# Ports_2.net
KiCad netlist of a schematic drawn in Altium Designer
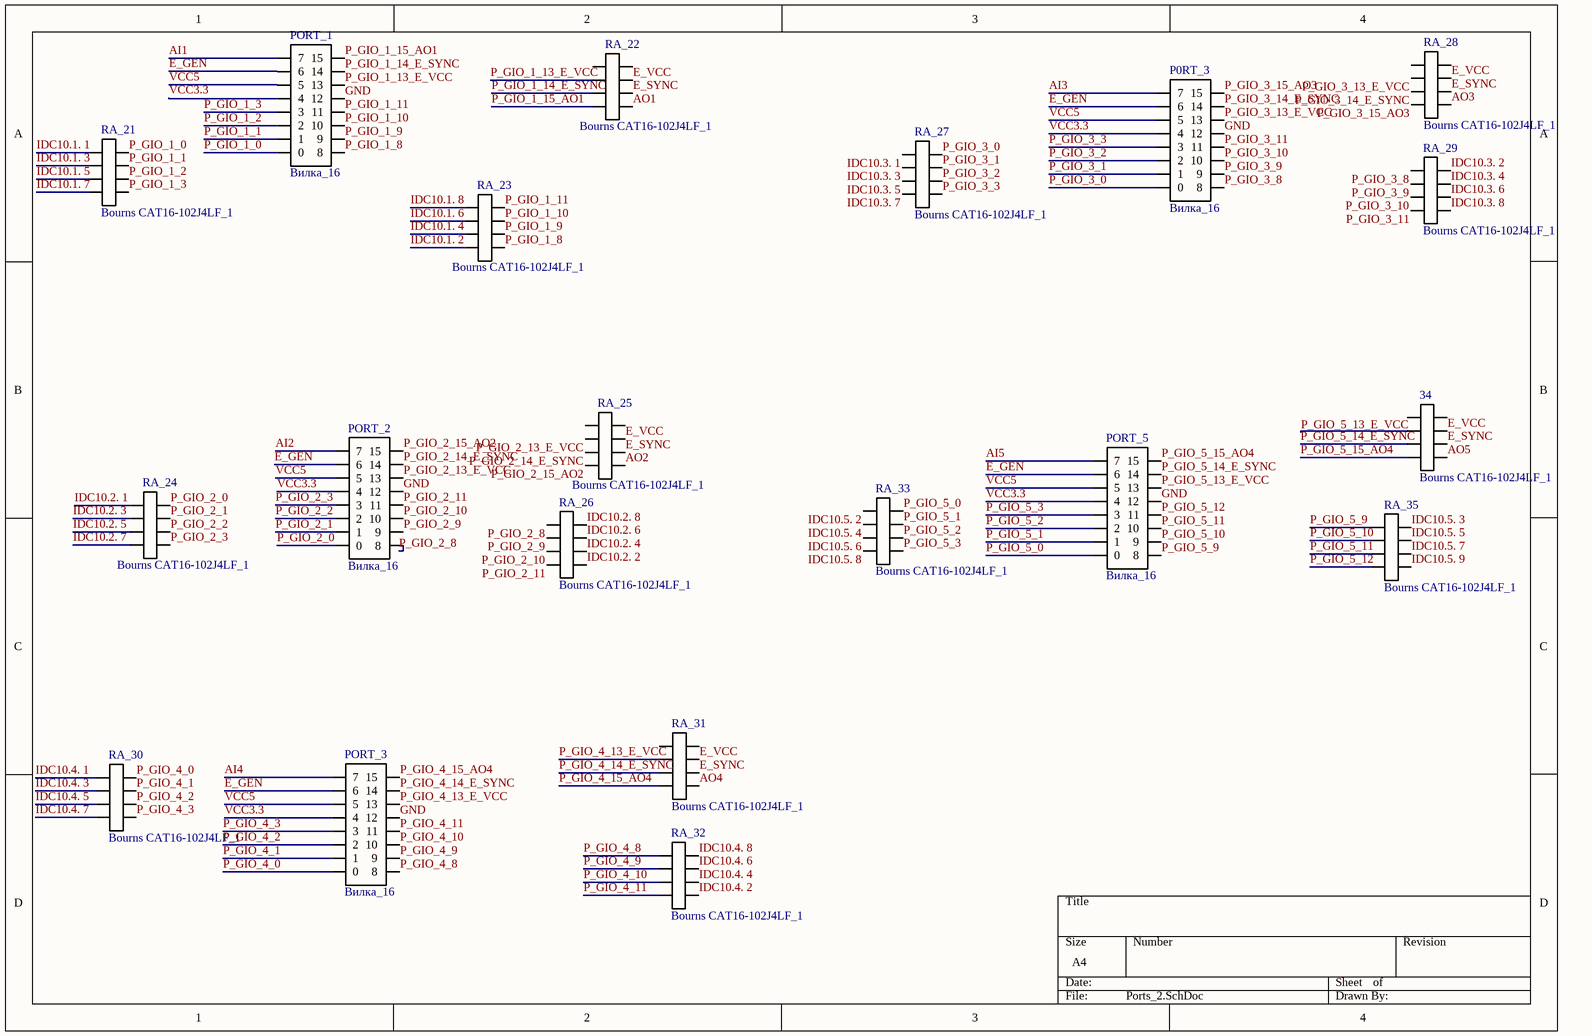
[diagram p0: Ports_2.SchDoc]

(export (version "E")
  (design (tool "Eeschema 10.0.6"))
  (components
    (comp (ref "34")
      (value "Bourns CAT16-102J4LF_1")
      (footprint "PcbLib1:CAT16-102J4LF_2")
      (libsource (lib "Library") (part "Bourns CAT16-102J4LF_1"))
    )
    (comp (ref "P0RT_3")
      (value "Вилка_16")
      (footprint "DS1013-16")
      (description "16_pin")
      (libsource (lib "Library") (part "DS1013-16"))
    )
    (comp (ref "PORT_1")
      (value "Вилка_16")
      (footprint "DS1013-16")
      (description "16_pin")
      (libsource (lib "Library") (part "DS1013-16"))
    )
    (comp (ref "PORT_2")
      (value "Вилка_16")
      (footprint "DS1013-16")
      (description "16_pin")
      (libsource (lib "Library") (part "DS1013-16"))
    )
    (comp (ref "PORT_3")
      (value "Вилка_16")
      (footprint "DS1013-16")
      (description "16_pin")
      (libsource (lib "Library") (part "DS1013-16"))
    )
    (comp (ref "PORT_5")
      (value "Вилка_16")
      (footprint "DS1013-16")
      (description "16_pin")
      (libsource (lib "Library") (part "DS1013-16"))
    )
    (comp (ref "RA_21")
      (value "Bourns CAT16-102J4LF_1")
      (footprint "PcbLib1:CAT16-102J4LF_2")
      (libsource (lib "Library") (part "Bourns CAT16-102J4LF_1"))
    )
    (comp (ref "RA_22")
      (value "Bourns CAT16-102J4LF_1")
      (footprint "PcbLib1:CAT16-102J4LF_2")
      (libsource (lib "Library") (part "Bourns CAT16-102J4LF_1"))
    )
    (comp (ref "RA_23")
      (value "Bourns CAT16-102J4LF_1")
      (footprint "PcbLib1:CAT16-102J4LF_2")
      (libsource (lib "Library") (part "Bourns CAT16-102J4LF_1"))
    )
    (comp (ref "RA_24")
      (value "Bourns CAT16-102J4LF_1")
      (footprint "PcbLib1:CAT16-102J4LF_2")
      (libsource (lib "Library") (part "Bourns CAT16-102J4LF_1"))
    )
    (comp (ref "RA_25")
      (value "Bourns CAT16-102J4LF_1")
      (footprint "PcbLib1:CAT16-102J4LF_2")
      (libsource (lib "Library") (part "Bourns CAT16-102J4LF_1"))
    )
    (comp (ref "RA_26")
      (value "Bourns CAT16-102J4LF_1")
      (footprint "PcbLib1:CAT16-102J4LF_2")
      (libsource (lib "Library") (part "Bourns CAT16-102J4LF_1"))
    )
    (comp (ref "RA_27")
      (value "Bourns CAT16-102J4LF_1")
      (footprint "PcbLib1:CAT16-102J4LF_2")
      (libsource (lib "Library") (part "Bourns CAT16-102J4LF_1"))
    )
    (comp (ref "RA_28")
      (value "Bourns CAT16-102J4LF_1")
      (footprint "PcbLib1:CAT16-102J4LF_2")
      (libsource (lib "Library") (part "Bourns CAT16-102J4LF_1"))
    )
    (comp (ref "RA_29")
      (value "Bourns CAT16-102J4LF_1")
      (footprint "PcbLib1:CAT16-102J4LF_2")
      (libsource (lib "Library") (part "Bourns CAT16-102J4LF_1"))
    )
    (comp (ref "RA_30")
      (value "Bourns CAT16-102J4LF_1")
      (footprint "PcbLib1:CAT16-102J4LF_2")
      (libsource (lib "Library") (part "Bourns CAT16-102J4LF_1"))
    )
    (comp (ref "RA_31")
      (value "Bourns CAT16-102J4LF_1")
      (footprint "PcbLib1:CAT16-102J4LF_2")
      (libsource (lib "Library") (part "Bourns CAT16-102J4LF_1"))
    )
    (comp (ref "RA_32")
      (value "Bourns CAT16-102J4LF_1")
      (footprint "PcbLib1:CAT16-102J4LF_2")
      (libsource (lib "Library") (part "Bourns CAT16-102J4LF_1"))
    )
    (comp (ref "RA_33")
      (value "Bourns CAT16-102J4LF_1")
      (footprint "PcbLib1:CAT16-102J4LF_2")
      (libsource (lib "Library") (part "Bourns CAT16-102J4LF_1"))
    )
    (comp (ref "RA_35")
      (value "Bourns CAT16-102J4LF_1")
      (footprint "PcbLib1:CAT16-102J4LF_2")
      (libsource (lib "Library") (part "Bourns CAT16-102J4LF_1"))
    )
  )
  (nets
    (net (code "1") (name "/AI1") (class "Default")
      (node (ref "PORT_1") (pin "7") (pinfunction "7_7") (pintype "passive"))
    )
    (net (code "2") (name "/AI2") (class "Default")
      (node (ref "PORT_2") (pin "7") (pinfunction "7_7") (pintype "passive"))
    )
    (net (code "3") (name "/AI3") (class "Default")
      (node (ref "P0RT_3") (pin "7") (pinfunction "7_7") (pintype "passive"))
    )
    (net (code "4") (name "/AI4") (class "Default")
      (node (ref "PORT_3") (pin "7") (pinfunction "7_7") (pintype "passive"))
    )
    (net (code "5") (name "/AI5") (class "Default")
      (node (ref "PORT_5") (pin "7") (pinfunction "7_7") (pintype "passive"))
    )
    (net (code "6") (name "/AO1") (class "Default")
      (node (ref "RA_22") (pin "4") (pinfunction "4_4") (pintype "passive"))
    )
    (net (code "7") (name "/AO2") (class "Default")
      (node (ref "RA_25") (pin "4") (pinfunction "4_4") (pintype "passive"))
    )
    (net (code "8") (name "/AO3") (class "Default")
      (node (ref "RA_28") (pin "0") (pinfunction "0_0") (pintype "passive"))
    )
    (net (code "9") (name "/AO4") (class "Default")
      (node (ref "RA_31") (pin "4") (pinfunction "4_4") (pintype "passive"))
    )
    (net (code "10") (name "/AO5") (class "Default")
      (node (ref "34") (pin "0") (pinfunction "0_0") (pintype "passive"))
    )
    (net (code "11") (name "/E_GEN") (class "Default")
      (node (ref "P0RT_3") (pin "6") (pinfunction "6_6") (pintype "passive"))
      (node (ref "PORT_1") (pin "6") (pinfunction "6_6") (pintype "passive"))
      (node (ref "PORT_2") (pin "6") (pinfunction "6_6") (pintype "passive"))
      (node (ref "PORT_3") (pin "6") (pinfunction "6_6") (pintype "passive"))
      (node (ref "PORT_5") (pin "6") (pinfunction "6_6") (pintype "passive"))
    )
    (net (code "12") (name "/E_SYNC") (class "Default")
      (node (ref "34") (pin "1") (pinfunction "1_1") (pintype "passive"))
      (node (ref "RA_22") (pin "5") (pinfunction "5_5") (pintype "passive"))
      (node (ref "RA_25") (pin "5") (pinfunction "5_5") (pintype "passive"))
      (node (ref "RA_28") (pin "1") (pinfunction "1_1") (pintype "passive"))
      (node (ref "RA_31") (pin "5") (pinfunction "5_5") (pintype "passive"))
    )
    (net (code "13") (name "/E_VCC") (class "Default")
      (node (ref "34") (pin "2") (pinfunction "2_2") (pintype "passive"))
      (node (ref "RA_22") (pin "6") (pinfunction "6_6") (pintype "passive"))
      (node (ref "RA_25") (pin "6") (pinfunction "6_6") (pintype "passive"))
      (node (ref "RA_28") (pin "2") (pinfunction "2_2") (pintype "passive"))
      (node (ref "RA_31") (pin "6") (pinfunction "6_6") (pintype "passive"))
    )
    (net (code "14") (name "/GND") (class "Default")
      (node (ref "P0RT_3") (pin "12") (pinfunction "12_12") (pintype "passive"))
      (node (ref "PORT_1") (pin "12") (pinfunction "12_12") (pintype "passive"))
      (node (ref "PORT_2") (pin "12") (pinfunction "12_12") (pintype "passive"))
      (node (ref "PORT_3") (pin "12") (pinfunction "12_12") (pintype "passive"))
      (node (ref "PORT_5") (pin "12") (pinfunction "12_12") (pintype "passive"))
    )
    (net (code "15") (name "/IDC10.1. 1") (class "Default")
      (node (ref "RA_21") (pin "4") (pinfunction "4_4") (pintype "passive"))
    )
    (net (code "16") (name "/IDC10.1. 2") (class "Default")
      (node (ref "RA_23") (pin "3") (pinfunction "3_3") (pintype "passive"))
    )
    (net (code "17") (name "/IDC10.1. 3") (class "Default")
      (node (ref "RA_21") (pin "5") (pinfunction "5_5") (pintype "passive"))
    )
    (net (code "18") (name "/IDC10.1. 4") (class "Default")
      (node (ref "RA_23") (pin "2") (pinfunction "2_2") (pintype "passive"))
    )
    (net (code "19") (name "/IDC10.1. 5") (class "Default")
      (node (ref "RA_21") (pin "6") (pinfunction "6_6") (pintype "passive"))
    )
    (net (code "20") (name "/IDC10.1. 6") (class "Default")
      (node (ref "RA_23") (pin "1") (pinfunction "1_1") (pintype "passive"))
    )
    (net (code "21") (name "/IDC10.1. 7") (class "Default")
      (node (ref "RA_21") (pin "7") (pinfunction "7_7") (pintype "passive"))
    )
    (net (code "22") (name "/IDC10.1. 8") (class "Default")
      (node (ref "RA_23") (pin "0") (pinfunction "0_0") (pintype "passive"))
    )
    (net (code "23") (name "/IDC10.2. 1") (class "Default")
      (node (ref "RA_24") (pin "0") (pinfunction "0_0") (pintype "passive"))
    )
    (net (code "24") (name "/IDC10.2. 2") (class "Default")
      (node (ref "RA_26") (pin "0") (pinfunction "0_0") (pintype "passive"))
    )
    (net (code "25") (name "/IDC10.2. 3") (class "Default")
      (node (ref "RA_24") (pin "1") (pinfunction "1_1") (pintype "passive"))
    )
    (net (code "26") (name "/IDC10.2. 4") (class "Default")
      (node (ref "RA_26") (pin "1") (pinfunction "1_1") (pintype "passive"))
    )
    (net (code "27") (name "/IDC10.2. 5") (class "Default")
      (node (ref "RA_24") (pin "2") (pinfunction "2_2") (pintype "passive"))
    )
    (net (code "28") (name "/IDC10.2. 6") (class "Default")
      (node (ref "RA_26") (pin "2") (pinfunction "2_2") (pintype "passive"))
    )
    (net (code "29") (name "/IDC10.2. 7") (class "Default")
      (node (ref "RA_24") (pin "3") (pinfunction "3_3") (pintype "passive"))
    )
    (net (code "30") (name "/IDC10.2. 8") (class "Default")
      (node (ref "RA_26") (pin "3") (pinfunction "3_3") (pintype "passive"))
    )
    (net (code "31") (name "/IDC10.3. 1") (class "Default")
      (node (ref "RA_27") (pin "4") (pinfunction "4_4") (pintype "passive"))
    )
    (net (code "32") (name "/IDC10.3. 2") (class "Default")
      (node (ref "RA_29") (pin "3") (pinfunction "3_3") (pintype "passive"))
    )
    (net (code "33") (name "/IDC10.3. 3") (class "Default")
      (node (ref "RA_27") (pin "5") (pinfunction "5_5") (pintype "passive"))
    )
    (net (code "34") (name "/IDC10.3. 4") (class "Default")
      (node (ref "RA_29") (pin "2") (pinfunction "2_2") (pintype "passive"))
    )
    (net (code "35") (name "/IDC10.3. 5") (class "Default")
      (node (ref "RA_27") (pin "6") (pinfunction "6_6") (pintype "passive"))
    )
    (net (code "36") (name "/IDC10.3. 6") (class "Default")
      (node (ref "RA_29") (pin "1") (pinfunction "1_1") (pintype "passive"))
    )
    (net (code "37") (name "/IDC10.3. 7") (class "Default")
      (node (ref "RA_27") (pin "7") (pinfunction "7_7") (pintype "passive"))
    )
    (net (code "38") (name "/IDC10.3. 8") (class "Default")
      (node (ref "RA_29") (pin "0") (pinfunction "0_0") (pintype "passive"))
    )
    (net (code "39") (name "/IDC10.4. 1") (class "Default")
      (node (ref "RA_30") (pin "4") (pinfunction "4_4") (pintype "passive"))
    )
    (net (code "40") (name "/IDC10.4. 2") (class "Default")
      (node (ref "RA_32") (pin "0") (pinfunction "0_0") (pintype "passive"))
    )
    (net (code "41") (name "/IDC10.4. 3") (class "Default")
      (node (ref "RA_30") (pin "5") (pinfunction "5_5") (pintype "passive"))
    )
    (net (code "42") (name "/IDC10.4. 4") (class "Default")
      (node (ref "RA_32") (pin "1") (pinfunction "1_1") (pintype "passive"))
    )
    (net (code "43") (name "/IDC10.4. 5") (class "Default")
      (node (ref "RA_30") (pin "6") (pinfunction "6_6") (pintype "passive"))
    )
    (net (code "44") (name "/IDC10.4. 6") (class "Default")
      (node (ref "RA_32") (pin "2") (pinfunction "2_2") (pintype "passive"))
    )
    (net (code "45") (name "/IDC10.4. 7") (class "Default")
      (node (ref "RA_30") (pin "7") (pinfunction "7_7") (pintype "passive"))
    )
    (net (code "46") (name "/IDC10.4. 8") (class "Default")
      (node (ref "RA_32") (pin "3") (pinfunction "3_3") (pintype "passive"))
    )
    (net (code "47") (name "/IDC10.5. 2") (class "Default")
      (node (ref "RA_33") (pin "4") (pinfunction "4_4") (pintype "passive"))
    )
    (net (code "48") (name "/IDC10.5. 3") (class "Default")
      (node (ref "RA_35") (pin "3") (pinfunction "3_3") (pintype "passive"))
    )
    (net (code "49") (name "/IDC10.5. 4") (class "Default")
      (node (ref "RA_33") (pin "5") (pinfunction "5_5") (pintype "passive"))
    )
    (net (code "50") (name "/IDC10.5. 5") (class "Default")
      (node (ref "RA_35") (pin "2") (pinfunction "2_2") (pintype "passive"))
    )
    (net (code "51") (name "/IDC10.5. 6") (class "Default")
      (node (ref "RA_33") (pin "6") (pinfunction "6_6") (pintype "passive"))
    )
    (net (code "52") (name "/IDC10.5. 7") (class "Default")
      (node (ref "RA_35") (pin "1") (pinfunction "1_1") (pintype "passive"))
    )
    (net (code "53") (name "/IDC10.5. 8") (class "Default")
      (node (ref "RA_33") (pin "7") (pinfunction "7_7") (pintype "passive"))
    )
    (net (code "54") (name "/IDC10.5. 9") (class "Default")
      (node (ref "RA_35") (pin "0") (pinfunction "0_0") (pintype "passive"))
    )
    (net (code "55") (name "/P_GIO_1_0") (class "Default")
      (node (ref "PORT_1") (pin "0") (pinfunction "0_0") (pintype "passive"))
      (node (ref "RA_21") (pin "3") (pinfunction "3_3") (pintype "passive"))
    )
    (net (code "56") (name "/P_GIO_1_1") (class "Default")
      (node (ref "PORT_1") (pin "1") (pinfunction "1_1") (pintype "passive"))
      (node (ref "RA_21") (pin "2") (pinfunction "2_2") (pintype "passive"))
    )
    (net (code "57") (name "/P_GIO_1_2") (class "Default")
      (node (ref "PORT_1") (pin "2") (pinfunction "2_2") (pintype "passive"))
      (node (ref "RA_21") (pin "1") (pinfunction "1_1") (pintype "passive"))
    )
    (net (code "58") (name "/P_GIO_1_3") (class "Default")
      (node (ref "PORT_1") (pin "3") (pinfunction "3_3") (pintype "passive"))
      (node (ref "RA_21") (pin "0") (pinfunction "0_0") (pintype "passive"))
    )
    (net (code "59") (name "/P_GIO_1_8") (class "Default")
      (node (ref "PORT_1") (pin "8") (pinfunction "8_8") (pintype "passive"))
      (node (ref "RA_23") (pin "4") (pinfunction "4_4") (pintype "passive"))
    )
    (net (code "60") (name "/P_GIO_1_9") (class "Default")
      (node (ref "PORT_1") (pin "9") (pinfunction "9_9") (pintype "passive"))
      (node (ref "RA_23") (pin "5") (pinfunction "5_5") (pintype "passive"))
    )
    (net (code "61") (name "/P_GIO_1_10") (class "Default")
      (node (ref "PORT_1") (pin "10") (pinfunction "10_10") (pintype "passive"))
      (node (ref "RA_23") (pin "6") (pinfunction "6_6") (pintype "passive"))
    )
    (net (code "62") (name "/P_GIO_1_11") (class "Default")
      (node (ref "PORT_1") (pin "11") (pinfunction "11_11") (pintype "passive"))
      (node (ref "RA_23") (pin "7") (pinfunction "7_7") (pintype "passive"))
    )
    (net (code "63") (name "/P_GIO_1_13_E_VCC") (class "Default")
      (node (ref "PORT_1") (pin "13") (pinfunction "13_13") (pintype "passive"))
      (node (ref "RA_22") (pin "1") (pinfunction "1_1") (pintype "passive"))
    )
    (net (code "64") (name "/P_GIO_1_14_E_SYNC") (class "Default")
      (node (ref "PORT_1") (pin "14") (pinfunction "14_14") (pintype "passive"))
      (node (ref "RA_22") (pin "2") (pinfunction "2_2") (pintype "passive"))
    )
    (net (code "65") (name "/P_GIO_1_15_AO1") (class "Default")
      (node (ref "PORT_1") (pin "15") (pinfunction "15_15") (pintype "passive"))
      (node (ref "RA_22") (pin "3") (pinfunction "3_3") (pintype "passive"))
    )
    (net (code "66") (name "/P_GIO_2_0") (class "Default")
      (node (ref "PORT_2") (pin "0") (pinfunction "0_0") (pintype "passive"))
      (node (ref "RA_24") (pin "7") (pinfunction "7_7") (pintype "passive"))
    )
    (net (code "67") (name "/P_GIO_2_1") (class "Default")
      (node (ref "PORT_2") (pin "1") (pinfunction "1_1") (pintype "passive"))
      (node (ref "RA_24") (pin "6") (pinfunction "6_6") (pintype "passive"))
    )
    (net (code "68") (name "/P_GIO_2_2") (class "Default")
      (node (ref "PORT_2") (pin "2") (pinfunction "2_2") (pintype "passive"))
      (node (ref "RA_24") (pin "5") (pinfunction "5_5") (pintype "passive"))
    )
    (net (code "69") (name "/P_GIO_2_3") (class "Default")
      (node (ref "PORT_2") (pin "3") (pinfunction "3_3") (pintype "passive"))
      (node (ref "RA_24") (pin "4") (pinfunction "4_4") (pintype "passive"))
    )
    (net (code "70") (name "/P_GIO_2_8") (class "Default")
      (node (ref "PORT_2") (pin "8") (pinfunction "8_8") (pintype "passive"))
      (node (ref "RA_26") (pin "4") (pinfunction "4_4") (pintype "passive"))
    )
    (net (code "71") (name "/P_GIO_2_9") (class "Default")
      (node (ref "PORT_2") (pin "9") (pinfunction "9_9") (pintype "passive"))
      (node (ref "RA_26") (pin "5") (pinfunction "5_5") (pintype "passive"))
    )
    (net (code "72") (name "/P_GIO_2_10") (class "Default")
      (node (ref "PORT_2") (pin "10") (pinfunction "10_10") (pintype "passive"))
      (node (ref "RA_26") (pin "6") (pinfunction "6_6") (pintype "passive"))
    )
    (net (code "73") (name "/P_GIO_2_11") (class "Default")
      (node (ref "PORT_2") (pin "11") (pinfunction "11_11") (pintype "passive"))
      (node (ref "RA_26") (pin "7") (pinfunction "7_7") (pintype "passive"))
    )
    (net (code "74") (name "/P_GIO_2_13_E_VCC") (class "Default")
      (node (ref "PORT_2") (pin "13") (pinfunction "13_13") (pintype "passive"))
      (node (ref "RA_25") (pin "1") (pinfunction "1_1") (pintype "passive"))
    )
    (net (code "75") (name "/P_GIO_2_14_E_SYNC") (class "Default")
      (node (ref "PORT_2") (pin "14") (pinfunction "14_14") (pintype "passive"))
      (node (ref "RA_25") (pin "2") (pinfunction "2_2") (pintype "passive"))
    )
    (net (code "76") (name "/P_GIO_2_15_AO2") (class "Default")
      (node (ref "PORT_2") (pin "15") (pinfunction "15_15") (pintype "passive"))
      (node (ref "RA_25") (pin "3") (pinfunction "3_3") (pintype "passive"))
    )
    (net (code "77") (name "/P_GIO_3_0") (class "Default")
      (node (ref "P0RT_3") (pin "0") (pinfunction "0_0") (pintype "passive"))
      (node (ref "RA_27") (pin "3") (pinfunction "3_3") (pintype "passive"))
    )
    (net (code "78") (name "/P_GIO_3_1") (class "Default")
      (node (ref "P0RT_3") (pin "1") (pinfunction "1_1") (pintype "passive"))
      (node (ref "RA_27") (pin "2") (pinfunction "2_2") (pintype "passive"))
    )
    (net (code "79") (name "/P_GIO_3_2") (class "Default")
      (node (ref "P0RT_3") (pin "2") (pinfunction "2_2") (pintype "passive"))
      (node (ref "RA_27") (pin "1") (pinfunction "1_1") (pintype "passive"))
    )
    (net (code "80") (name "/P_GIO_3_3") (class "Default")
      (node (ref "P0RT_3") (pin "3") (pinfunction "3_3") (pintype "passive"))
      (node (ref "RA_27") (pin "0") (pinfunction "0_0") (pintype "passive"))
    )
    (net (code "81") (name "/P_GIO_3_8") (class "Default")
      (node (ref "P0RT_3") (pin "8") (pinfunction "8_8") (pintype "passive"))
      (node (ref "RA_29") (pin "4") (pinfunction "4_4") (pintype "passive"))
    )
    (net (code "82") (name "/P_GIO_3_9") (class "Default")
      (node (ref "P0RT_3") (pin "9") (pinfunction "9_9") (pintype "passive"))
      (node (ref "RA_29") (pin "5") (pinfunction "5_5") (pintype "passive"))
    )
    (net (code "83") (name "/P_GIO_3_10") (class "Default")
      (node (ref "P0RT_3") (pin "10") (pinfunction "10_10") (pintype "passive"))
      (node (ref "RA_29") (pin "6") (pinfunction "6_6") (pintype "passive"))
    )
    (net (code "84") (name "/P_GIO_3_11") (class "Default")
      (node (ref "P0RT_3") (pin "11") (pinfunction "11_11") (pintype "passive"))
      (node (ref "RA_29") (pin "7") (pinfunction "7_7") (pintype "passive"))
    )
    (net (code "85") (name "/P_GIO_3_13_E_VCC") (class "Default")
      (node (ref "P0RT_3") (pin "13") (pinfunction "13_13") (pintype "passive"))
      (node (ref "RA_28") (pin "5") (pinfunction "5_5") (pintype "passive"))
    )
    (net (code "86") (name "/P_GIO_3_14_E_SYNC") (class "Default")
      (node (ref "P0RT_3") (pin "14") (pinfunction "14_14") (pintype "passive"))
      (node (ref "RA_28") (pin "6") (pinfunction "6_6") (pintype "passive"))
    )
    (net (code "87") (name "/P_GIO_3_15_AO3") (class "Default")
      (node (ref "P0RT_3") (pin "15") (pinfunction "15_15") (pintype "passive"))
      (node (ref "RA_28") (pin "7") (pinfunction "7_7") (pintype "passive"))
    )
    (net (code "88") (name "/P_GIO_4_0") (class "Default")
      (node (ref "PORT_3") (pin "0") (pinfunction "0_0") (pintype "passive"))
      (node (ref "RA_30") (pin "3") (pinfunction "3_3") (pintype "passive"))
    )
    (net (code "89") (name "/P_GIO_4_1") (class "Default")
      (node (ref "PORT_3") (pin "1") (pinfunction "1_1") (pintype "passive"))
      (node (ref "RA_30") (pin "2") (pinfunction "2_2") (pintype "passive"))
    )
    (net (code "90") (name "/P_GIO_4_2") (class "Default")
      (node (ref "PORT_3") (pin "2") (pinfunction "2_2") (pintype "passive"))
      (node (ref "RA_30") (pin "1") (pinfunction "1_1") (pintype "passive"))
    )
    (net (code "91") (name "/P_GIO_4_3") (class "Default")
      (node (ref "PORT_3") (pin "3") (pinfunction "3_3") (pintype "passive"))
      (node (ref "RA_30") (pin "0") (pinfunction "0_0") (pintype "passive"))
    )
    (net (code "92") (name "/P_GIO_4_8") (class "Default")
      (node (ref "PORT_3") (pin "8") (pinfunction "8_8") (pintype "passive"))
      (node (ref "RA_32") (pin "4") (pinfunction "4_4") (pintype "passive"))
    )
    (net (code "93") (name "/P_GIO_4_9") (class "Default")
      (node (ref "PORT_3") (pin "9") (pinfunction "9_9") (pintype "passive"))
      (node (ref "RA_32") (pin "5") (pinfunction "5_5") (pintype "passive"))
    )
    (net (code "94") (name "/P_GIO_4_10") (class "Default")
      (node (ref "PORT_3") (pin "10") (pinfunction "10_10") (pintype "passive"))
      (node (ref "RA_32") (pin "6") (pinfunction "6_6") (pintype "passive"))
    )
    (net (code "95") (name "/P_GIO_4_11") (class "Default")
      (node (ref "PORT_3") (pin "11") (pinfunction "11_11") (pintype "passive"))
      (node (ref "RA_32") (pin "7") (pinfunction "7_7") (pintype "passive"))
    )
    (net (code "96") (name "/P_GIO_4_13_E_VCC") (class "Default")
      (node (ref "PORT_3") (pin "13") (pinfunction "13_13") (pintype "passive"))
      (node (ref "RA_31") (pin "1") (pinfunction "1_1") (pintype "passive"))
    )
    (net (code "97") (name "/P_GIO_4_14_E_SYNC") (class "Default")
      (node (ref "PORT_3") (pin "14") (pinfunction "14_14") (pintype "passive"))
      (node (ref "RA_31") (pin "2") (pinfunction "2_2") (pintype "passive"))
    )
    (net (code "98") (name "/P_GIO_4_15_AO4") (class "Default")
      (node (ref "PORT_3") (pin "15") (pinfunction "15_15") (pintype "passive"))
      (node (ref "RA_31") (pin "3") (pinfunction "3_3") (pintype "passive"))
    )
    (net (code "99") (name "/P_GIO_5_0") (class "Default")
      (node (ref "PORT_5") (pin "0") (pinfunction "0_0") (pintype "passive"))
      (node (ref "RA_33") (pin "3") (pinfunction "3_3") (pintype "passive"))
    )
    (net (code "100") (name "/P_GIO_5_1") (class "Default")
      (node (ref "PORT_5") (pin "1") (pinfunction "1_1") (pintype "passive"))
      (node (ref "RA_33") (pin "2") (pinfunction "2_2") (pintype "passive"))
    )
    (net (code "101") (name "/P_GIO_5_2") (class "Default")
      (node (ref "PORT_5") (pin "2") (pinfunction "2_2") (pintype "passive"))
      (node (ref "RA_33") (pin "1") (pinfunction "1_1") (pintype "passive"))
    )
    (net (code "102") (name "/P_GIO_5_3") (class "Default")
      (node (ref "PORT_5") (pin "3") (pinfunction "3_3") (pintype "passive"))
      (node (ref "RA_33") (pin "0") (pinfunction "0_0") (pintype "passive"))
    )
    (net (code "103") (name "/P_GIO_5_9") (class "Default")
      (node (ref "PORT_5") (pin "8") (pinfunction "8_8") (pintype "passive"))
      (node (ref "RA_35") (pin "4") (pinfunction "4_4") (pintype "passive"))
    )
    (net (code "104") (name "/P_GIO_5_10") (class "Default")
      (node (ref "PORT_5") (pin "9") (pinfunction "9_9") (pintype "passive"))
      (node (ref "RA_35") (pin "5") (pinfunction "5_5") (pintype "passive"))
    )
    (net (code "105") (name "/P_GIO_5_11") (class "Default")
      (node (ref "PORT_5") (pin "10") (pinfunction "10_10") (pintype "passive"))
      (node (ref "RA_35") (pin "6") (pinfunction "6_6") (pintype "passive"))
    )
    (net (code "106") (name "/P_GIO_5_12") (class "Default")
      (node (ref "PORT_5") (pin "11") (pinfunction "11_11") (pintype "passive"))
      (node (ref "RA_35") (pin "7") (pinfunction "7_7") (pintype "passive"))
    )
    (net (code "107") (name "/P_GIO_5_13_E_VCC") (class "Default")
      (node (ref "34") (pin "5") (pinfunction "5_5") (pintype "passive"))
      (node (ref "PORT_5") (pin "13") (pinfunction "13_13") (pintype "passive"))
    )
    (net (code "108") (name "/P_GIO_5_14_E_SYNC") (class "Default")
      (node (ref "34") (pin "6") (pinfunction "6_6") (pintype "passive"))
      (node (ref "PORT_5") (pin "14") (pinfunction "14_14") (pintype "passive"))
    )
    (net (code "109") (name "/P_GIO_5_15_AO4") (class "Default")
      (node (ref "34") (pin "7") (pinfunction "7_7") (pintype "passive"))
      (node (ref "PORT_5") (pin "15") (pinfunction "15_15") (pintype "passive"))
    )
    (net (code "110") (name "/VCC3.3") (class "Default")
      (node (ref "P0RT_3") (pin "4") (pinfunction "4_4") (pintype "passive"))
      (node (ref "PORT_1") (pin "4") (pinfunction "4_4") (pintype "passive"))
      (node (ref "PORT_2") (pin "4") (pinfunction "4_4") (pintype "passive"))
      (node (ref "PORT_3") (pin "4") (pinfunction "4_4") (pintype "passive"))
      (node (ref "PORT_5") (pin "4") (pinfunction "4_4") (pintype "passive"))
    )
    (net (code "111") (name "/VCC5") (class "Default")
      (node (ref "P0RT_3") (pin "5") (pinfunction "5_5") (pintype "passive"))
      (node (ref "PORT_1") (pin "5") (pinfunction "5_5") (pintype "passive"))
      (node (ref "PORT_2") (pin "5") (pinfunction "5_5") (pintype "passive"))
      (node (ref "PORT_3") (pin "5") (pinfunction "5_5") (pintype "passive"))
      (node (ref "PORT_5") (pin "5") (pinfunction "5_5") (pintype "passive"))
    )
    (net (code "112") (name "unconnected-(34-Pad3)") (class "Default")
      (node (ref "34") (pin "3") (pinfunction "3_3") (pintype "passive"))
    )
    (net (code "113") (name "unconnected-(34-Pad4)") (class "Default")
      (node (ref "34") (pin "4") (pinfunction "4_4") (pintype "passive"))
    )
    (net (code "114") (name "unconnected-(RA_22-Pad0)") (class "Default")
      (node (ref "RA_22") (pin "0") (pinfunction "0_0") (pintype "passive"))
    )
    (net (code "115") (name "unconnected-(RA_22-Pad7)") (class "Default")
      (node (ref "RA_22") (pin "7") (pinfunction "7_7") (pintype "passive"))
    )
    (net (code "116") (name "unconnected-(RA_25-Pad0)") (class "Default")
      (node (ref "RA_25") (pin "0") (pinfunction "0_0") (pintype "passive"))
    )
    (net (code "117") (name "unconnected-(RA_25-Pad7)") (class "Default")
      (node (ref "RA_25") (pin "7") (pinfunction "7_7") (pintype "passive"))
    )
    (net (code "118") (name "unconnected-(RA_28-Pad3)") (class "Default")
      (node (ref "RA_28") (pin "3") (pinfunction "3_3") (pintype "passive"))
    )
    (net (code "119") (name "unconnected-(RA_28-Pad4)") (class "Default")
      (node (ref "RA_28") (pin "4") (pinfunction "4_4") (pintype "passive"))
    )
    (net (code "120") (name "unconnected-(RA_31-Pad0)") (class "Default")
      (node (ref "RA_31") (pin "0") (pinfunction "0_0") (pintype "passive"))
    )
    (net (code "121") (name "unconnected-(RA_31-Pad7)") (class "Default")
      (node (ref "RA_31") (pin "7") (pinfunction "7_7") (pintype "passive"))
    )
  )
)
